# Arduino_nano.net
KiCad netlist of a schematic drawn in Altium Designer
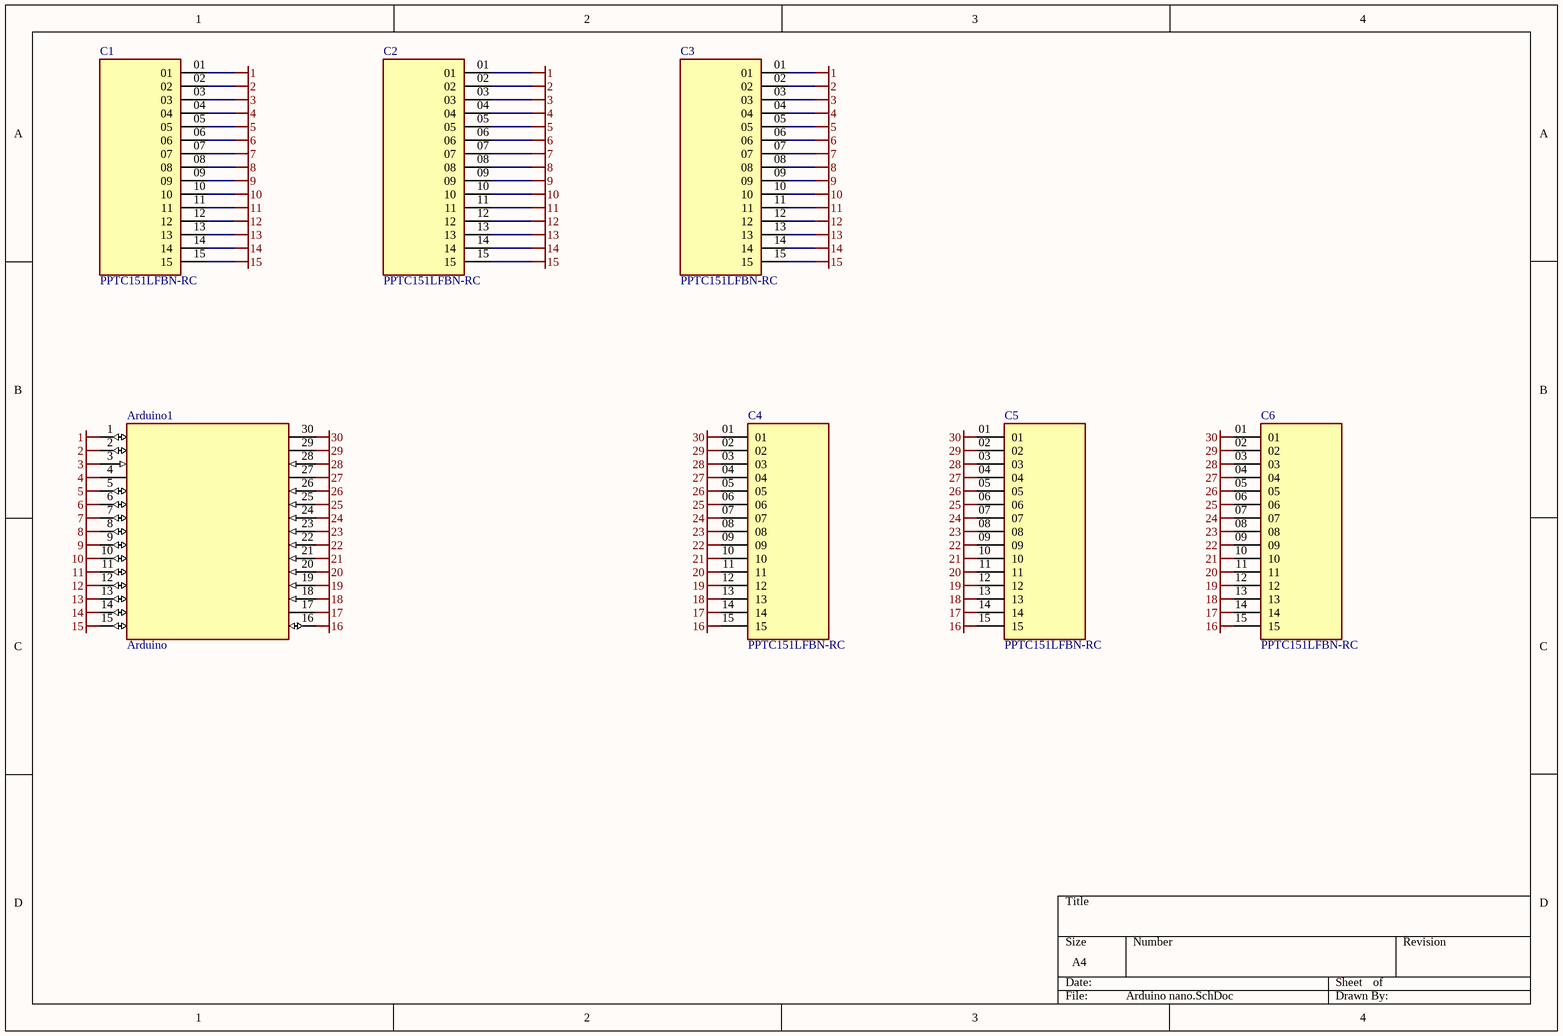
[diagram p0: Arduino nano.SchDoc]

(export (version "E")
  (design (tool "Eeschema 10.0.6"))
  (components
    (comp (ref "Arduino1")
      (value "Arduino")
      (footprint "MODULE_A000005")
      (fields (field (name "MANUFACTURER PART NUMBER") "A000005"))
      (libsource (lib "Schlib1") (part "A000005"))
    )
    (comp (ref "C1")
      (value "PPTC151LFBN-RC")
      (footprint "SAMTEC_DW-15-12-G-S-807")
      (fields (field (name "MANUFACTURER") "Sullins"))
      (libsource (lib "Schlib1") (part "PPTC151LFBN-RC"))
    )
    (comp (ref "C2")
      (value "PPTC151LFBN-RC")
      (footprint "SAMTEC_DW-15-12-G-S-807")
      (fields (field (name "MANUFACTURER") "Sullins"))
      (libsource (lib "Schlib1") (part "PPTC151LFBN-RC"))
    )
    (comp (ref "C3")
      (value "PPTC151LFBN-RC")
      (footprint "SAMTEC_DW-15-12-G-S-807")
      (fields (field (name "MANUFACTURER") "Sullins"))
      (libsource (lib "Schlib1") (part "PPTC151LFBN-RC"))
    )
    (comp (ref "C4")
      (value "PPTC151LFBN-RC")
      (footprint "SAMTEC_DW-15-12-G-S-807")
      (fields (field (name "MANUFACTURER") "Sullins"))
      (libsource (lib "") (part "PPTC151LFBN-RC_1"))
    )
    (comp (ref "C5")
      (value "PPTC151LFBN-RC")
      (footprint "SAMTEC_DW-15-12-G-S-807")
      (fields (field (name "MANUFACTURER") "Sullins"))
      (libsource (lib "") (part "PPTC151LFBN-RC_1"))
    )
    (comp (ref "C6")
      (value "PPTC151LFBN-RC")
      (footprint "SAMTEC_DW-15-12-G-S-807")
      (fields (field (name "MANUFACTURER") "Sullins"))
      (libsource (lib "") (part "PPTC151LFBN-RC_1"))
    )
  )
  (nets
    (net (code "1") (name "1") (class "Default")
      (node (ref "Arduino1") (pin "1") (pinfunction "D0/TX_1") (pintype "bidirectional"))
      (node (ref "C1") (pin "01") (pinfunction "01_01") (pintype "passive"))
      (node (ref "C2") (pin "01") (pinfunction "01_01") (pintype "passive"))
      (node (ref "C3") (pin "01") (pinfunction "01_01") (pintype "passive"))
    )
    (net (code "2") (name "2") (class "Default")
      (node (ref "Arduino1") (pin "2") (pinfunction "D1/RX_2") (pintype "bidirectional"))
      (node (ref "C1") (pin "02") (pinfunction "02_02") (pintype "passive"))
      (node (ref "C2") (pin "02") (pinfunction "02_02") (pintype "passive"))
      (node (ref "C3") (pin "02") (pinfunction "02_02") (pintype "passive"))
    )
    (net (code "3") (name "3") (class "Default")
      (node (ref "Arduino1") (pin "3") (pinfunction "RESET_1_3") (pintype "input"))
      (node (ref "C1") (pin "03") (pinfunction "03_03") (pintype "passive"))
      (node (ref "C2") (pin "03") (pinfunction "03_03") (pintype "passive"))
      (node (ref "C3") (pin "03") (pinfunction "03_03") (pintype "passive"))
    )
    (net (code "4") (name "4") (class "Default")
      (node (ref "Arduino1") (pin "4") (pinfunction "GND_1_4") (pintype "power_in"))
      (node (ref "C1") (pin "04") (pinfunction "04_04") (pintype "passive"))
      (node (ref "C2") (pin "04") (pinfunction "04_04") (pintype "passive"))
      (node (ref "C3") (pin "04") (pinfunction "04_04") (pintype "passive"))
    )
    (net (code "5") (name "5") (class "Default")
      (node (ref "Arduino1") (pin "5") (pinfunction "D2_5") (pintype "bidirectional"))
      (node (ref "C1") (pin "05") (pinfunction "05_05") (pintype "passive"))
      (node (ref "C2") (pin "05") (pinfunction "05_05") (pintype "passive"))
      (node (ref "C3") (pin "05") (pinfunction "05_05") (pintype "passive"))
    )
    (net (code "6") (name "6") (class "Default")
      (node (ref "Arduino1") (pin "6") (pinfunction "D3_6") (pintype "bidirectional"))
      (node (ref "C1") (pin "06") (pinfunction "06_06") (pintype "passive"))
      (node (ref "C2") (pin "06") (pinfunction "06_06") (pintype "passive"))
      (node (ref "C3") (pin "06") (pinfunction "06_06") (pintype "passive"))
    )
    (net (code "7") (name "7") (class "Default")
      (node (ref "Arduino1") (pin "7") (pinfunction "D4_7") (pintype "bidirectional"))
      (node (ref "C1") (pin "07") (pinfunction "07_07") (pintype "passive"))
      (node (ref "C2") (pin "07") (pinfunction "07_07") (pintype "passive"))
      (node (ref "C3") (pin "07") (pinfunction "07_07") (pintype "passive"))
    )
    (net (code "8") (name "8") (class "Default")
      (node (ref "Arduino1") (pin "8") (pinfunction "D5_8") (pintype "bidirectional"))
      (node (ref "C1") (pin "08") (pinfunction "08_08") (pintype "passive"))
      (node (ref "C2") (pin "08") (pinfunction "08_08") (pintype "passive"))
      (node (ref "C3") (pin "08") (pinfunction "08_08") (pintype "passive"))
    )
    (net (code "9") (name "9") (class "Default")
      (node (ref "Arduino1") (pin "9") (pinfunction "D6_9") (pintype "bidirectional"))
      (node (ref "C1") (pin "09") (pinfunction "09_09") (pintype "passive"))
      (node (ref "C2") (pin "09") (pinfunction "09_09") (pintype "passive"))
      (node (ref "C3") (pin "09") (pinfunction "09_09") (pintype "passive"))
    )
    (net (code "10") (name "10") (class "Default")
      (node (ref "Arduino1") (pin "10") (pinfunction "D7_10") (pintype "bidirectional"))
      (node (ref "C1") (pin "10") (pinfunction "10_10") (pintype "passive"))
      (node (ref "C2") (pin "10") (pinfunction "10_10") (pintype "passive"))
      (node (ref "C3") (pin "10") (pinfunction "10_10") (pintype "passive"))
    )
    (net (code "11") (name "11") (class "Default")
      (node (ref "Arduino1") (pin "11") (pinfunction "D8_11") (pintype "bidirectional"))
      (node (ref "C1") (pin "11") (pinfunction "11_11") (pintype "passive"))
      (node (ref "C2") (pin "11") (pinfunction "11_11") (pintype "passive"))
      (node (ref "C3") (pin "11") (pinfunction "11_11") (pintype "passive"))
    )
    (net (code "12") (name "12") (class "Default")
      (node (ref "Arduino1") (pin "12") (pinfunction "D9_12") (pintype "bidirectional"))
      (node (ref "C1") (pin "12") (pinfunction "12_12") (pintype "passive"))
      (node (ref "C2") (pin "12") (pinfunction "12_12") (pintype "passive"))
      (node (ref "C3") (pin "12") (pinfunction "12_12") (pintype "passive"))
    )
    (net (code "13") (name "13") (class "Default")
      (node (ref "Arduino1") (pin "13") (pinfunction "D10_13") (pintype "bidirectional"))
      (node (ref "C1") (pin "13") (pinfunction "13_13") (pintype "passive"))
      (node (ref "C2") (pin "13") (pinfunction "13_13") (pintype "passive"))
      (node (ref "C3") (pin "13") (pinfunction "13_13") (pintype "passive"))
    )
    (net (code "14") (name "14") (class "Default")
      (node (ref "Arduino1") (pin "14") (pinfunction "D11_14") (pintype "bidirectional"))
      (node (ref "C1") (pin "14") (pinfunction "14_14") (pintype "passive"))
      (node (ref "C2") (pin "14") (pinfunction "14_14") (pintype "passive"))
      (node (ref "C3") (pin "14") (pinfunction "14_14") (pintype "passive"))
    )
    (net (code "15") (name "15") (class "Default")
      (node (ref "Arduino1") (pin "15") (pinfunction "D12_15") (pintype "bidirectional"))
      (node (ref "C1") (pin "15") (pinfunction "15_15") (pintype "passive"))
      (node (ref "C2") (pin "15") (pinfunction "15_15") (pintype "passive"))
      (node (ref "C3") (pin "15") (pinfunction "15_15") (pintype "passive"))
    )
    (net (code "16") (name "16") (class "Default")
      (node (ref "Arduino1") (pin "16") (pinfunction "D13_16") (pintype "bidirectional"))
      (node (ref "C4") (pin "15") (pinfunction "15_15") (pintype "passive"))
      (node (ref "C5") (pin "15") (pinfunction "15_15") (pintype "passive"))
      (node (ref "C6") (pin "15") (pinfunction "15_15") (pintype "passive"))
    )
    (net (code "17") (name "17") (class "Default")
      (node (ref "Arduino1") (pin "17") (pinfunction "3V3_17") (pintype "power_in"))
      (node (ref "C4") (pin "14") (pinfunction "14_14") (pintype "passive"))
      (node (ref "C5") (pin "14") (pinfunction "14_14") (pintype "passive"))
      (node (ref "C6") (pin "14") (pinfunction "14_14") (pintype "passive"))
    )
    (net (code "18") (name "18") (class "Default")
      (node (ref "Arduino1") (pin "18") (pinfunction "AREF_18") (pintype "input"))
      (node (ref "C4") (pin "13") (pinfunction "13_13") (pintype "passive"))
      (node (ref "C5") (pin "13") (pinfunction "13_13") (pintype "passive"))
      (node (ref "C6") (pin "13") (pinfunction "13_13") (pintype "passive"))
    )
    (net (code "19") (name "19") (class "Default")
      (node (ref "Arduino1") (pin "19") (pinfunction "A0_19") (pintype "input"))
      (node (ref "C4") (pin "12") (pinfunction "12_12") (pintype "passive"))
      (node (ref "C5") (pin "12") (pinfunction "12_12") (pintype "passive"))
      (node (ref "C6") (pin "12") (pinfunction "12_12") (pintype "passive"))
    )
    (net (code "20") (name "20") (class "Default")
      (node (ref "Arduino1") (pin "20") (pinfunction "A1_20") (pintype "input"))
      (node (ref "C4") (pin "11") (pinfunction "11_11") (pintype "passive"))
      (node (ref "C5") (pin "11") (pinfunction "11_11") (pintype "passive"))
      (node (ref "C6") (pin "11") (pinfunction "11_11") (pintype "passive"))
    )
    (net (code "21") (name "21") (class "Default")
      (node (ref "Arduino1") (pin "21") (pinfunction "A2_21") (pintype "input"))
      (node (ref "C4") (pin "10") (pinfunction "10_10") (pintype "passive"))
      (node (ref "C5") (pin "10") (pinfunction "10_10") (pintype "passive"))
      (node (ref "C6") (pin "10") (pinfunction "10_10") (pintype "passive"))
    )
    (net (code "22") (name "22") (class "Default")
      (node (ref "Arduino1") (pin "22") (pinfunction "A3_22") (pintype "input"))
      (node (ref "C4") (pin "09") (pinfunction "09_09") (pintype "passive"))
      (node (ref "C5") (pin "09") (pinfunction "09_09") (pintype "passive"))
      (node (ref "C6") (pin "09") (pinfunction "09_09") (pintype "passive"))
    )
    (net (code "23") (name "23") (class "Default")
      (node (ref "Arduino1") (pin "23") (pinfunction "A4_23") (pintype "input"))
      (node (ref "C4") (pin "08") (pinfunction "08_08") (pintype "passive"))
      (node (ref "C5") (pin "08") (pinfunction "08_08") (pintype "passive"))
      (node (ref "C6") (pin "08") (pinfunction "08_08") (pintype "passive"))
    )
    (net (code "24") (name "24") (class "Default")
      (node (ref "Arduino1") (pin "24") (pinfunction "A5_24") (pintype "input"))
      (node (ref "C4") (pin "07") (pinfunction "07_07") (pintype "passive"))
      (node (ref "C5") (pin "07") (pinfunction "07_07") (pintype "passive"))
      (node (ref "C6") (pin "07") (pinfunction "07_07") (pintype "passive"))
    )
    (net (code "25") (name "25") (class "Default")
      (node (ref "Arduino1") (pin "25") (pinfunction "A6_25") (pintype "input"))
      (node (ref "C4") (pin "06") (pinfunction "06_06") (pintype "passive"))
      (node (ref "C5") (pin "06") (pinfunction "06_06") (pintype "passive"))
      (node (ref "C6") (pin "06") (pinfunction "06_06") (pintype "passive"))
    )
    (net (code "26") (name "26") (class "Default")
      (node (ref "Arduino1") (pin "26") (pinfunction "A7_26") (pintype "input"))
      (node (ref "C4") (pin "05") (pinfunction "05_05") (pintype "passive"))
      (node (ref "C5") (pin "05") (pinfunction "05_05") (pintype "passive"))
      (node (ref "C6") (pin "05") (pinfunction "05_05") (pintype "passive"))
    )
    (net (code "27") (name "27") (class "Default")
      (node (ref "Arduino1") (pin "27") (pinfunction "5V_27") (pintype "power_in"))
      (node (ref "C4") (pin "04") (pinfunction "04_04") (pintype "passive"))
      (node (ref "C5") (pin "04") (pinfunction "04_04") (pintype "passive"))
      (node (ref "C6") (pin "04") (pinfunction "04_04") (pintype "passive"))
    )
    (net (code "28") (name "28") (class "Default")
      (node (ref "Arduino1") (pin "28") (pinfunction "RESET_2_28") (pintype "input"))
      (node (ref "C4") (pin "03") (pinfunction "03_03") (pintype "passive"))
      (node (ref "C5") (pin "03") (pinfunction "03_03") (pintype "passive"))
      (node (ref "C6") (pin "03") (pinfunction "03_03") (pintype "passive"))
    )
    (net (code "29") (name "29") (class "Default")
      (node (ref "Arduino1") (pin "29") (pinfunction "GND_2_29") (pintype "power_in"))
      (node (ref "C4") (pin "02") (pinfunction "02_02") (pintype "passive"))
      (node (ref "C5") (pin "02") (pinfunction "02_02") (pintype "passive"))
      (node (ref "C6") (pin "02") (pinfunction "02_02") (pintype "passive"))
    )
    (net (code "30") (name "30") (class "Default")
      (node (ref "Arduino1") (pin "30") (pinfunction "VIN_30") (pintype "power_in"))
      (node (ref "C4") (pin "01") (pinfunction "01_01") (pintype "passive"))
      (node (ref "C5") (pin "01") (pinfunction "01_01") (pintype "passive"))
      (node (ref "C6") (pin "01") (pinfunction "01_01") (pintype "passive"))
    )
  )
)
